# Grove_-_Finger-clip_Heart_Rate_Sensor_v1.net
KiCad netlist of a schematic drawn in EAGLE
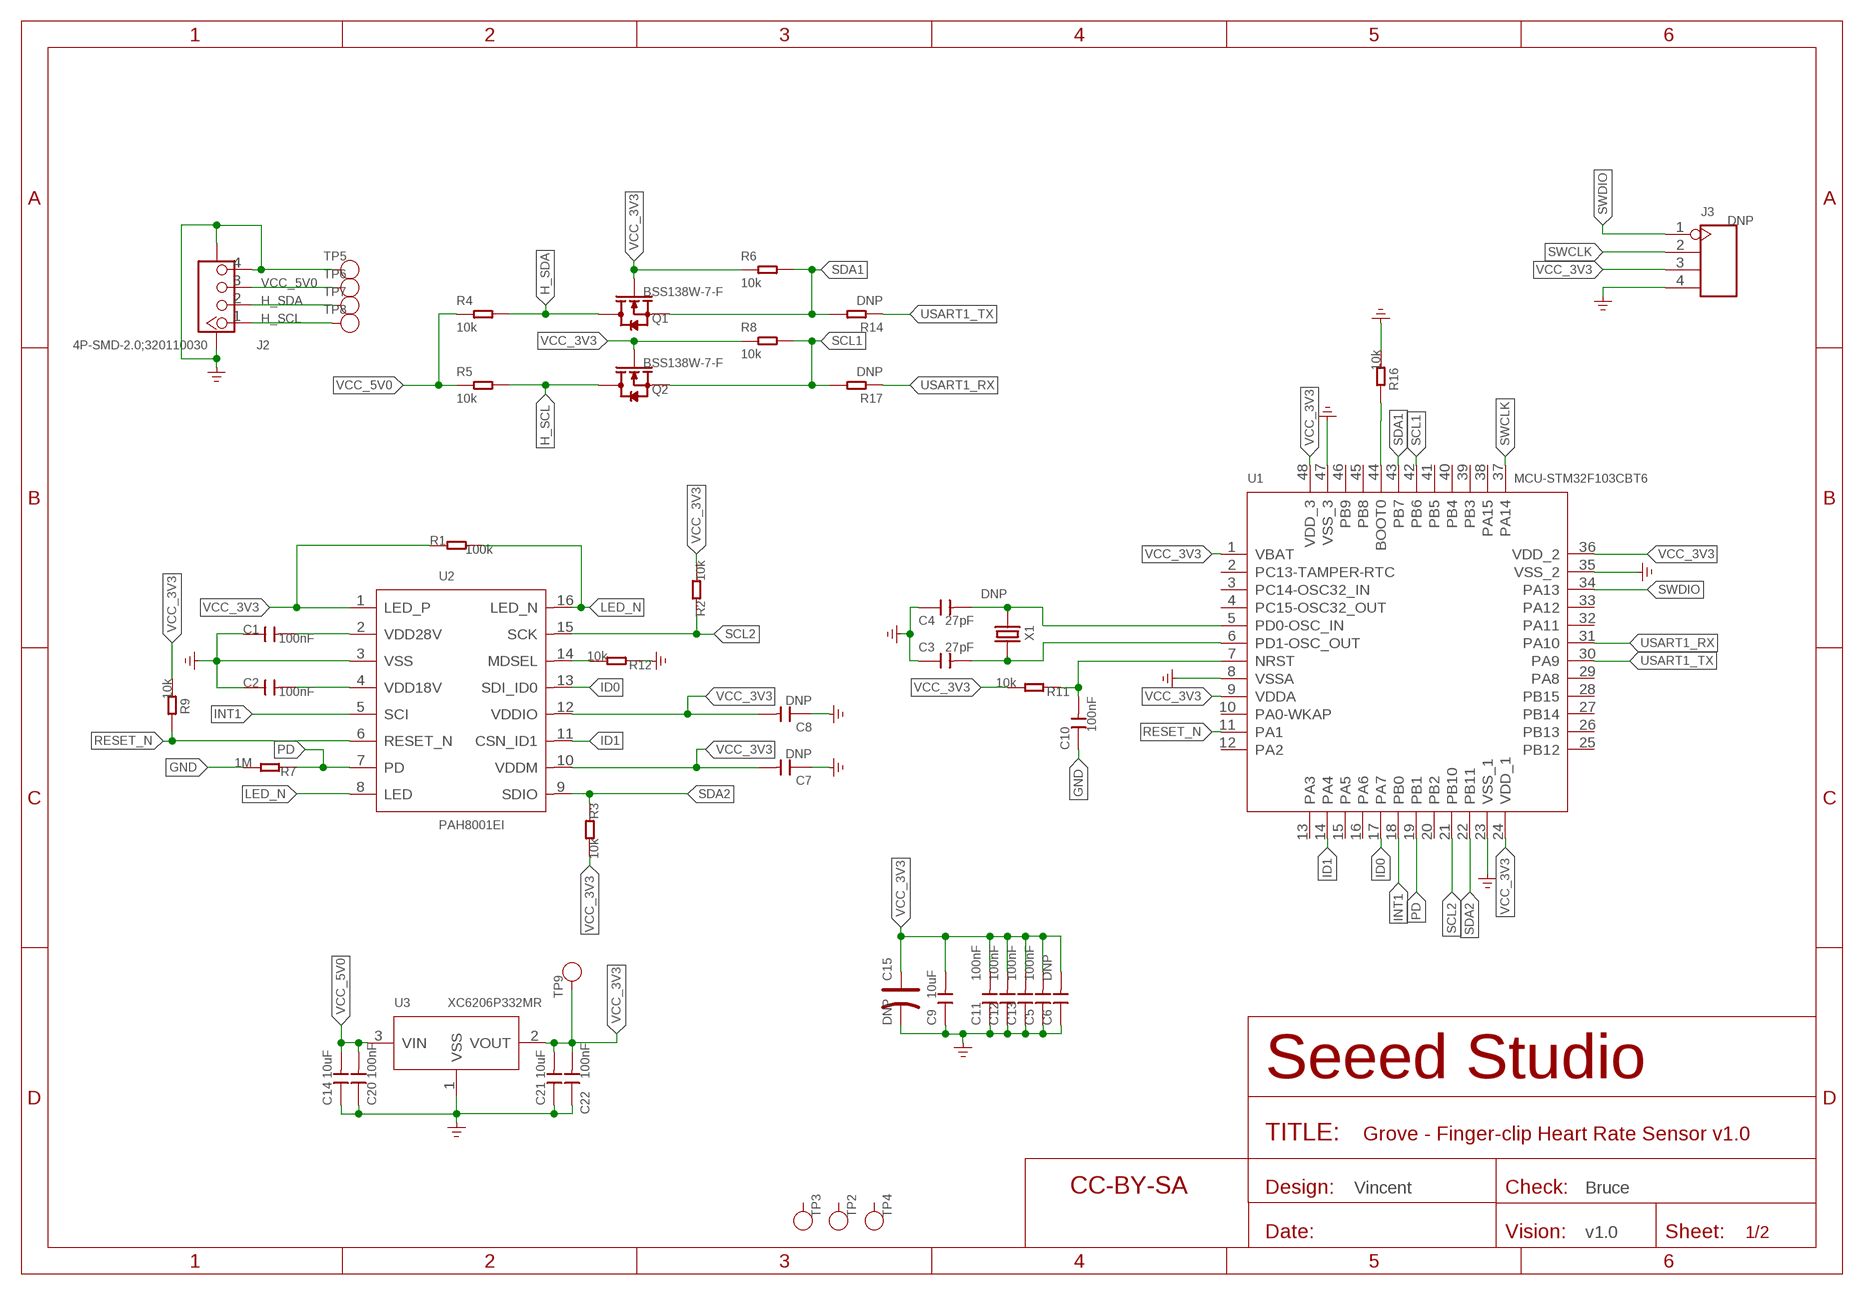
[diagram p0: schematic, sheet 1]

(export (version "E")
  (design (tool "Eeschema 10.0.6"))
  (components
    (comp (ref "C1")
      (value "100nF")
      (footprint "eagle-import:C0402")
      (libsource (lib "eagle-import") (part "CAP-0402"))
    )
    (comp (ref "C2")
      (value "100nF")
      (footprint "eagle-import:C0402")
      (libsource (lib "eagle-import") (part "CAP-0402"))
    )
    (comp (ref "C3")
      (value "27pF")
      (footprint "eagle-import:C0402")
      (libsource (lib "eagle-import") (part "CAP-0402"))
    )
    (comp (ref "C4")
      (value "27pF")
      (footprint "eagle-import:C0402")
      (libsource (lib "eagle-import") (part "CAP-0402"))
    )
    (comp (ref "C5")
      (value "100nF")
      (footprint "eagle-import:C0402")
      (libsource (lib "eagle-import") (part "CAP-0402"))
    )
    (comp (ref "C6")
      (value "DNP")
      (footprint "eagle-import:C0402")
      (libsource (lib "eagle-import") (part "CAP-0402"))
    )
    (comp (ref "C7")
      (value "DNP")
      (footprint "eagle-import:C0402")
      (libsource (lib "eagle-import") (part "CAP-0402"))
    )
    (comp (ref "C8")
      (value "DNP")
      (footprint "eagle-import:C0402")
      (libsource (lib "eagle-import") (part "CAP-0402"))
    )
    (comp (ref "C9")
      (value "10uF")
      (footprint "eagle-import:C0603")
      (libsource (lib "eagle-import") (part "CAP-0603"))
    )
    (comp (ref "C10")
      (value "100nF")
      (footprint "eagle-import:C0402")
      (libsource (lib "eagle-import") (part "CAP-0402"))
    )
    (comp (ref "C11")
      (value "100nF")
      (footprint "eagle-import:C0402")
      (libsource (lib "eagle-import") (part "CAP-0402"))
    )
    (comp (ref "C12")
      (value "100nF")
      (footprint "eagle-import:C0402")
      (libsource (lib "eagle-import") (part "CAP-0402"))
    )
    (comp (ref "C13")
      (value "100nF")
      (footprint "eagle-import:C0402")
      (libsource (lib "eagle-import") (part "CAP-0402"))
    )
    (comp (ref "C14")
      (value "10uF")
      (footprint "eagle-import:C0603")
      (libsource (lib "eagle-import") (part "CAP-0603"))
    )
    (comp (ref "C15")
      (value "DNP")
      (footprint "eagle-import:AVX-A")
      (libsource (lib "eagle-import") (part "CAP-POLAR-AVX-A"))
    )
    (comp (ref "C20")
      (value "100nF")
      (footprint "eagle-import:C0402")
      (libsource (lib "eagle-import") (part "CAP-0402"))
    )
    (comp (ref "C21")
      (value "10uF")
      (footprint "eagle-import:C0603")
      (libsource (lib "eagle-import") (part "CAP-0603"))
    )
    (comp (ref "C22")
      (value "100nF")
      (footprint "eagle-import:C0402")
      (libsource (lib "eagle-import") (part "CAP-0402"))
    )
    (comp (ref "J2")
      (value "4P-SMD-2.0;320110030")
      (footprint "eagle-import:4P-SMD-2.0")
      (libsource (lib "eagle-import") (part "GROVE-CONNECTOR-SMD'DD'"))
    )
    (comp (ref "J3")
      (value "DNP")
      (footprint "eagle-import:4P-2.54-65_35MIL")
      (libsource (lib "eagle-import") (part "HEADER-4P-65/35MIL"))
    )
    (comp (ref "Q1")
      (value "BSS138W-7-F")
      (footprint "eagle-import:SOT-323")
      (libsource (lib "eagle-import") (part "MOSFET-N'SI1304BDL'"))
    )
    (comp (ref "Q2")
      (value "BSS138W-7-F")
      (footprint "eagle-import:SOT-323")
      (libsource (lib "eagle-import") (part "MOSFET-N'SI1304BDL'"))
    )
    (comp (ref "R1")
      (value "100k")
      (footprint "eagle-import:R0402")
      (libsource (lib "eagle-import") (part "RES-0402"))
    )
    (comp (ref "R2")
      (value "10k")
      (footprint "eagle-import:R0402")
      (libsource (lib "eagle-import") (part "RES-0402"))
    )
    (comp (ref "R3")
      (value "10k")
      (footprint "eagle-import:R0402")
      (libsource (lib "eagle-import") (part "RES-0402"))
    )
    (comp (ref "R4")
      (value "10k")
      (footprint "eagle-import:R0402")
      (libsource (lib "eagle-import") (part "RES-0402"))
    )
    (comp (ref "R5")
      (value "10k")
      (footprint "eagle-import:R0402")
      (libsource (lib "eagle-import") (part "RES-0402"))
    )
    (comp (ref "R6")
      (value "10k")
      (footprint "eagle-import:R0402")
      (libsource (lib "eagle-import") (part "RES-0402"))
    )
    (comp (ref "R7")
      (value "1M")
      (footprint "eagle-import:R0402")
      (libsource (lib "eagle-import") (part "RES-0402"))
    )
    (comp (ref "R8")
      (value "10k")
      (footprint "eagle-import:R0402")
      (libsource (lib "eagle-import") (part "RES-0402"))
    )
    (comp (ref "R9")
      (value "10k")
      (footprint "eagle-import:R0402")
      (libsource (lib "eagle-import") (part "RES-0402"))
    )
    (comp (ref "R11")
      (value "10k")
      (footprint "eagle-import:R0402")
      (libsource (lib "eagle-import") (part "RES-0402"))
    )
    (comp (ref "R12")
      (value "10k")
      (footprint "eagle-import:R0402")
      (libsource (lib "eagle-import") (part "RES-0402"))
    )
    (comp (ref "R14")
      (value "DNP")
      (footprint "eagle-import:R0402")
      (libsource (lib "eagle-import") (part "RES-0402"))
    )
    (comp (ref "R16")
      (value "10k")
      (footprint "eagle-import:R0402")
      (libsource (lib "eagle-import") (part "RES-0402"))
    )
    (comp (ref "R17")
      (value "DNP")
      (footprint "eagle-import:R0402")
      (libsource (lib "eagle-import") (part "RES-0402"))
    )
    (comp (ref "TP2")
      (value "DNP")
      (footprint "eagle-import:TP-D45MIL")
      (libsource (lib "eagle-import") (part "PAD-TEST-POINT'4545'"))
    )
    (comp (ref "TP3")
      (value "DNP")
      (footprint "eagle-import:TP-D45MIL")
      (libsource (lib "eagle-import") (part "PAD-TEST-POINT'4545'"))
    )
    (comp (ref "TP4")
      (value "DNP")
      (footprint "eagle-import:TP-D45MIL")
      (libsource (lib "eagle-import") (part "PAD-TEST-POINT'4545'"))
    )
    (comp (ref "TP5")
      (value "DNP")
      (footprint "eagle-import:TP-D45MIL")
      (libsource (lib "eagle-import") (part "PAD-TEST-POINT'4545'"))
    )
    (comp (ref "TP6")
      (value "DNP")
      (footprint "eagle-import:TP-D45MIL")
      (libsource (lib "eagle-import") (part "PAD-TEST-POINT'4545'"))
    )
    (comp (ref "TP7")
      (value "DNP")
      (footprint "eagle-import:TP-D45MIL")
      (libsource (lib "eagle-import") (part "PAD-TEST-POINT'4545'"))
    )
    (comp (ref "TP8")
      (value "DNP")
      (footprint "eagle-import:TP-D45MIL")
      (libsource (lib "eagle-import") (part "PAD-TEST-POINT'4545'"))
    )
    (comp (ref "TP9")
      (value "DNP")
      (footprint "eagle-import:TP-D45MIL")
      (libsource (lib "eagle-import") (part "PAD-TEST-POINT'4545'"))
    )
    (comp (ref "U$1")
      (value "SEEEDSTUDIO-OPEN-SCH-FRAME")
      (footprint "eagle-import:SEEEDSTUDIO-PCB-FRAME")
      (libsource (lib "eagle-import") (part "SEEEDSTUDIO-OPEN-SCH-FRAME"))
    )
    (comp (ref "U1")
      (value "MCU-STM32F103CBT6")
      (footprint "eagle-import:TEMPLATE_LQFP48")
      (libsource (lib "eagle-import") (part "TEMPLATE_MCU-STM32F103CBT6"))
    )
    (comp (ref "U2")
      (value "PAH8001EI")
      (footprint "eagle-import:16P-SMD-L4.7_W3_H1MM")
      (libsource (lib "eagle-import") (part "PAH8001EI-QG"))
    )
    (comp (ref "U3")
      (value "XC6206P332MR")
      (footprint "eagle-import:SOT-23")
      (libsource (lib "eagle-import") (part "PMIC-XC6206PMR"))
    )
    (comp (ref "X1")
      (value "DNP")
      (footprint "eagle-import:2P-SMD-L5.0_W3.2MM")
      (libsource (lib "eagle-import") (part "CRYSTAL'5032'"))
    )
  )
  (nets
    (net (code "1") (name "BOOT0") (class "Default")
      (node (ref "R16") (pin "2") (pinfunction "2_2") (pintype "passive"))
      (node (ref "U1") (pin "44") (pinfunction "BOOT0_44") (pintype "bidirectional"))
    )
    (net (code "2") (name "GND") (class "Default")
      (node (ref "C1") (pin "1") (pinfunction "1_1") (pintype "passive"))
      (node (ref "C10") (pin "1") (pinfunction "1_1") (pintype "passive"))
      (node (ref "C11") (pin "1") (pinfunction "1_1") (pintype "passive"))
      (node (ref "C12") (pin "1") (pinfunction "1_1") (pintype "passive"))
      (node (ref "C13") (pin "1") (pinfunction "1_1") (pintype "passive"))
      (node (ref "C14") (pin "1") (pinfunction "1_1") (pintype "passive"))
      (node (ref "C15") (pin "-") (pinfunction "-_-") (pintype "passive"))
      (node (ref "C2") (pin "1") (pinfunction "1_1") (pintype "passive"))
      (node (ref "C20") (pin "1") (pinfunction "1_1") (pintype "passive"))
      (node (ref "C21") (pin "1") (pinfunction "1_1") (pintype "passive"))
      (node (ref "C22") (pin "1") (pinfunction "1_1") (pintype "passive"))
      (node (ref "C3") (pin "1") (pinfunction "1_1") (pintype "passive"))
      (node (ref "C4") (pin "1") (pinfunction "1_1") (pintype "passive"))
      (node (ref "C5") (pin "1") (pinfunction "1_1") (pintype "passive"))
      (node (ref "C6") (pin "1") (pinfunction "1_1") (pintype "passive"))
      (node (ref "C7") (pin "1") (pinfunction "1_1") (pintype "passive"))
      (node (ref "C8") (pin "1") (pinfunction "1_1") (pintype "passive"))
      (node (ref "C9") (pin "1") (pinfunction "1_1") (pintype "passive"))
      (node (ref "J2") (pin "4") (pinfunction "4_4") (pintype "bidirectional"))
      (node (ref "J2") (pin "SS1") (pinfunction "SS1_SS1") (pintype "bidirectional"))
      (node (ref "J2") (pin "SS2") (pinfunction "SS2_SS2") (pintype "bidirectional"))
      (node (ref "J3") (pin "4") (pinfunction "P$4_4") (pintype "bidirectional"))
      (node (ref "R12") (pin "1") (pinfunction "1_1") (pintype "passive"))
      (node (ref "R16") (pin "1") (pinfunction "1_1") (pintype "passive"))
      (node (ref "R7") (pin "2") (pinfunction "2_2") (pintype "passive"))
      (node (ref "TP5") (pin "T") (pinfunction "T_T") (pintype "bidirectional"))
      (node (ref "U1") (pin "23") (pinfunction "VSS_1_23") (pintype "bidirectional"))
      (node (ref "U1") (pin "35") (pinfunction "VSS_2_35") (pintype "bidirectional"))
      (node (ref "U1") (pin "47") (pinfunction "VSS_3_47") (pintype "bidirectional"))
      (node (ref "U1") (pin "8") (pinfunction "VSSA_8") (pintype "bidirectional"))
      (node (ref "U2") (pin "3") (pinfunction "VSS_3") (pintype "bidirectional"))
      (node (ref "U3") (pin "1") (pinfunction "VSS_1") (pintype "power_in"))
    )
    (net (code "3") (name "H_SCL") (class "Default")
      (node (ref "J2") (pin "1") (pinfunction "1_1") (pintype "bidirectional"))
      (node (ref "Q2") (pin "3") (pinfunction "D_3") (pintype "passive"))
      (node (ref "R5") (pin "2") (pinfunction "2_2") (pintype "passive"))
      (node (ref "TP8") (pin "T") (pinfunction "T_T") (pintype "bidirectional"))
    )
    (net (code "4") (name "H_SDA") (class "Default")
      (node (ref "J2") (pin "2") (pinfunction "2_2") (pintype "bidirectional"))
      (node (ref "Q1") (pin "3") (pinfunction "D_3") (pintype "passive"))
      (node (ref "R4") (pin "2") (pinfunction "2_2") (pintype "passive"))
      (node (ref "TP7") (pin "T") (pinfunction "T_T") (pintype "bidirectional"))
    )
    (net (code "5") (name "ID0") (class "Default")
      (node (ref "U1") (pin "17") (pinfunction "PA7_17") (pintype "bidirectional"))
      (node (ref "U2") (pin "13") (pinfunction "SDI_ID0_13") (pintype "bidirectional"))
    )
    (net (code "6") (name "ID1") (class "Default")
      (node (ref "U1") (pin "14") (pinfunction "PA4_14") (pintype "bidirectional"))
      (node (ref "U2") (pin "11") (pinfunction "CSN_ID1_11") (pintype "bidirectional"))
    )
    (net (code "7") (name "INT1") (class "Default")
      (node (ref "U1") (pin "18") (pinfunction "PB0_18") (pintype "bidirectional"))
      (node (ref "U2") (pin "5") (pinfunction "SCI_5") (pintype "bidirectional"))
    )
    (net (code "8") (name "LED_N") (class "Default")
      (node (ref "R1") (pin "2") (pinfunction "2_2") (pintype "passive"))
      (node (ref "U2") (pin "16") (pinfunction "LED_N_16") (pintype "bidirectional"))
      (node (ref "U2") (pin "8") (pinfunction "LED_8") (pintype "bidirectional"))
    )
    (net (code "9") (name "Net-(U1-NRST)") (class "Default")
      (node (ref "C10") (pin "2") (pinfunction "2_2") (pintype "passive"))
      (node (ref "R11") (pin "1") (pinfunction "1_1") (pintype "passive"))
      (node (ref "U1") (pin "7") (pinfunction "NRST_7") (pintype "bidirectional"))
    )
    (net (code "10") (name "Net-(U1-PD0-OSC_IN)") (class "Default")
      (node (ref "C4") (pin "2") (pinfunction "2_2") (pintype "passive"))
      (node (ref "U1") (pin "5") (pinfunction "PD0-OSC_IN_5") (pintype "bidirectional"))
      (node (ref "X1") (pin "1") (pinfunction "1_1") (pintype "passive"))
    )
    (net (code "11") (name "Net-(U1-PD1-OSC_OUT)") (class "Default")
      (node (ref "C3") (pin "2") (pinfunction "2_2") (pintype "passive"))
      (node (ref "U1") (pin "6") (pinfunction "PD1-OSC_OUT_6") (pintype "bidirectional"))
      (node (ref "X1") (pin "2") (pinfunction "2_2") (pintype "passive"))
    )
    (net (code "12") (name "Net-(U2-MDSEL)") (class "Default")
      (node (ref "R12") (pin "2") (pinfunction "2_2") (pintype "passive"))
      (node (ref "U2") (pin "14") (pinfunction "MDSEL_14") (pintype "bidirectional"))
    )
    (net (code "13") (name "Net-(U2-VDD18V)") (class "Default")
      (node (ref "C2") (pin "2") (pinfunction "2_2") (pintype "passive"))
      (node (ref "U2") (pin "4") (pinfunction "VDD18V_4") (pintype "bidirectional"))
    )
    (net (code "14") (name "Net-(U2-VDD28V)") (class "Default")
      (node (ref "C1") (pin "2") (pinfunction "2_2") (pintype "passive"))
      (node (ref "U2") (pin "2") (pinfunction "VDD28V_2") (pintype "bidirectional"))
    )
    (net (code "15") (name "PD") (class "Default")
      (node (ref "R7") (pin "1") (pinfunction "1_1") (pintype "passive"))
      (node (ref "U1") (pin "19") (pinfunction "PB1_19") (pintype "bidirectional"))
      (node (ref "U2") (pin "7") (pinfunction "PD_7") (pintype "bidirectional"))
    )
    (net (code "16") (name "RESET_N") (class "Default")
      (node (ref "R9") (pin "2") (pinfunction "2_2") (pintype "passive"))
      (node (ref "U1") (pin "11") (pinfunction "PA1_11") (pintype "bidirectional"))
      (node (ref "U2") (pin "6") (pinfunction "RESET_N_6") (pintype "bidirectional"))
    )
    (net (code "17") (name "SCL1") (class "Default")
      (node (ref "Q2") (pin "2") (pinfunction "S_2") (pintype "passive"))
      (node (ref "R17") (pin "2") (pinfunction "2_2") (pintype "passive"))
      (node (ref "R8") (pin "2") (pinfunction "2_2") (pintype "passive"))
      (node (ref "U1") (pin "42") (pinfunction "PB6_42") (pintype "bidirectional"))
    )
    (net (code "18") (name "SCL2") (class "Default")
      (node (ref "R2") (pin "1") (pinfunction "1_1") (pintype "passive"))
      (node (ref "U1") (pin "21") (pinfunction "PB10_21") (pintype "bidirectional"))
      (node (ref "U2") (pin "15") (pinfunction "SCK_15") (pintype "bidirectional"))
    )
    (net (code "19") (name "SDA1") (class "Default")
      (node (ref "Q1") (pin "2") (pinfunction "S_2") (pintype "passive"))
      (node (ref "R14") (pin "2") (pinfunction "2_2") (pintype "passive"))
      (node (ref "R6") (pin "2") (pinfunction "2_2") (pintype "passive"))
      (node (ref "U1") (pin "43") (pinfunction "PB7_43") (pintype "bidirectional"))
    )
    (net (code "20") (name "SDA2") (class "Default")
      (node (ref "R3") (pin "1") (pinfunction "1_1") (pintype "passive"))
      (node (ref "U1") (pin "22") (pinfunction "PB11_22") (pintype "bidirectional"))
      (node (ref "U2") (pin "9") (pinfunction "SDIO_9") (pintype "bidirectional"))
    )
    (net (code "21") (name "SWCLK") (class "Default")
      (node (ref "J3") (pin "2") (pinfunction "P$2_2") (pintype "bidirectional"))
      (node (ref "U1") (pin "37") (pinfunction "PA14_37") (pintype "bidirectional"))
    )
    (net (code "22") (name "SWDIO") (class "Default")
      (node (ref "J3") (pin "1") (pinfunction "P$1_1") (pintype "bidirectional"))
      (node (ref "U1") (pin "34") (pinfunction "PA13_34") (pintype "bidirectional"))
    )
    (net (code "23") (name "USART1_RX") (class "Default")
      (node (ref "R17") (pin "1") (pinfunction "1_1") (pintype "passive"))
      (node (ref "U1") (pin "31") (pinfunction "PA10_31") (pintype "bidirectional"))
    )
    (net (code "24") (name "USART1_TX") (class "Default")
      (node (ref "R14") (pin "1") (pinfunction "1_1") (pintype "passive"))
      (node (ref "U1") (pin "30") (pinfunction "PA9_30") (pintype "bidirectional"))
    )
    (net (code "25") (name "VCC_3V3") (class "Default")
      (node (ref "C11") (pin "2") (pinfunction "2_2") (pintype "passive"))
      (node (ref "C12") (pin "2") (pinfunction "2_2") (pintype "passive"))
      (node (ref "C13") (pin "2") (pinfunction "2_2") (pintype "passive"))
      (node (ref "C15") (pin "+") (pinfunction "+_+") (pintype "passive"))
      (node (ref "C21") (pin "2") (pinfunction "2_2") (pintype "passive"))
      (node (ref "C22") (pin "2") (pinfunction "2_2") (pintype "passive"))
      (node (ref "C5") (pin "2") (pinfunction "2_2") (pintype "passive"))
      (node (ref "C6") (pin "2") (pinfunction "2_2") (pintype "passive"))
      (node (ref "C7") (pin "2") (pinfunction "2_2") (pintype "passive"))
      (node (ref "C8") (pin "2") (pinfunction "2_2") (pintype "passive"))
      (node (ref "C9") (pin "2") (pinfunction "2_2") (pintype "passive"))
      (node (ref "J3") (pin "3") (pinfunction "P$3_3") (pintype "bidirectional"))
      (node (ref "Q1") (pin "1") (pinfunction "G_1") (pintype "passive"))
      (node (ref "Q2") (pin "1") (pinfunction "G_1") (pintype "passive"))
      (node (ref "R1") (pin "1") (pinfunction "1_1") (pintype "passive"))
      (node (ref "R11") (pin "2") (pinfunction "2_2") (pintype "passive"))
      (node (ref "R2") (pin "2") (pinfunction "2_2") (pintype "passive"))
      (node (ref "R3") (pin "2") (pinfunction "2_2") (pintype "passive"))
      (node (ref "R6") (pin "1") (pinfunction "1_1") (pintype "passive"))
      (node (ref "R8") (pin "1") (pinfunction "1_1") (pintype "passive"))
      (node (ref "R9") (pin "1") (pinfunction "1_1") (pintype "passive"))
      (node (ref "TP9") (pin "T") (pinfunction "T_T") (pintype "bidirectional"))
      (node (ref "U1") (pin "1") (pinfunction "VBAT_1") (pintype "bidirectional"))
      (node (ref "U1") (pin "24") (pinfunction "VDD_1_24") (pintype "bidirectional"))
      (node (ref "U1") (pin "36") (pinfunction "VDD_2_36") (pintype "bidirectional"))
      (node (ref "U1") (pin "48") (pinfunction "VDD_3_48") (pintype "bidirectional"))
      (node (ref "U1") (pin "9") (pinfunction "VDDA_9") (pintype "bidirectional"))
      (node (ref "U2") (pin "1") (pinfunction "LED_P_1") (pintype "bidirectional"))
      (node (ref "U2") (pin "10") (pinfunction "VDDM_10") (pintype "bidirectional"))
      (node (ref "U2") (pin "12") (pinfunction "VDDIO_12") (pintype "bidirectional"))
      (node (ref "U3") (pin "2") (pinfunction "VOUT_2") (pintype "output"))
    )
    (net (code "26") (name "VCC_5V0") (class "Default")
      (node (ref "C14") (pin "2") (pinfunction "2_2") (pintype "passive"))
      (node (ref "C20") (pin "2") (pinfunction "2_2") (pintype "passive"))
      (node (ref "J2") (pin "3") (pinfunction "3_3") (pintype "bidirectional"))
      (node (ref "R4") (pin "1") (pinfunction "1_1") (pintype "passive"))
      (node (ref "R5") (pin "1") (pinfunction "1_1") (pintype "passive"))
      (node (ref "TP6") (pin "T") (pinfunction "T_T") (pintype "bidirectional"))
      (node (ref "U3") (pin "3") (pinfunction "VIN_3") (pintype "input"))
    )
    (net (code "27") (name "unconnected-(TP2-PadT)") (class "Default")
      (node (ref "TP2") (pin "T") (pinfunction "T_T") (pintype "bidirectional"))
    )
    (net (code "28") (name "unconnected-(TP3-PadT)") (class "Default")
      (node (ref "TP3") (pin "T") (pinfunction "T_T") (pintype "bidirectional"))
    )
    (net (code "29") (name "unconnected-(TP4-PadT)") (class "Default")
      (node (ref "TP4") (pin "T") (pinfunction "T_T") (pintype "bidirectional"))
    )
    (net (code "30") (name "unconnected-(U1-PA0-WKAP-Pad10)") (class "Default")
      (node (ref "U1") (pin "10") (pinfunction "PA0-WKAP_10") (pintype "bidirectional"))
    )
    (net (code "31") (name "unconnected-(U1-PA2-Pad12)") (class "Default")
      (node (ref "U1") (pin "12") (pinfunction "PA2_12") (pintype "bidirectional"))
    )
    (net (code "32") (name "unconnected-(U1-PA3-Pad13)") (class "Default")
      (node (ref "U1") (pin "13") (pinfunction "PA3_13") (pintype "bidirectional"))
    )
    (net (code "33") (name "unconnected-(U1-PA5-Pad15)") (class "Default")
      (node (ref "U1") (pin "15") (pinfunction "PA5_15") (pintype "bidirectional"))
    )
    (net (code "34") (name "unconnected-(U1-PA6-Pad16)") (class "Default")
      (node (ref "U1") (pin "16") (pinfunction "PA6_16") (pintype "bidirectional"))
    )
    (net (code "35") (name "unconnected-(U1-PA8-Pad29)") (class "Default")
      (node (ref "U1") (pin "29") (pinfunction "PA8_29") (pintype "bidirectional"))
    )
    (net (code "36") (name "unconnected-(U1-PA11-Pad32)") (class "Default")
      (node (ref "U1") (pin "32") (pinfunction "PA11_32") (pintype "bidirectional"))
    )
    (net (code "37") (name "unconnected-(U1-PA12-Pad33)") (class "Default")
      (node (ref "U1") (pin "33") (pinfunction "PA12_33") (pintype "bidirectional"))
    )
    (net (code "38") (name "unconnected-(U1-PA15-Pad38)") (class "Default")
      (node (ref "U1") (pin "38") (pinfunction "PA15_38") (pintype "bidirectional"))
    )
    (net (code "39") (name "unconnected-(U1-PB2-Pad20)") (class "Default")
      (node (ref "U1") (pin "20") (pinfunction "PB2_20") (pintype "bidirectional"))
    )
    (net (code "40") (name "unconnected-(U1-PB3-Pad39)") (class "Default")
      (node (ref "U1") (pin "39") (pinfunction "PB3_39") (pintype "bidirectional"))
    )
    (net (code "41") (name "unconnected-(U1-PB4-Pad40)") (class "Default")
      (node (ref "U1") (pin "40") (pinfunction "PB4_40") (pintype "bidirectional"))
    )
    (net (code "42") (name "unconnected-(U1-PB5-Pad41)") (class "Default")
      (node (ref "U1") (pin "41") (pinfunction "PB5_41") (pintype "bidirectional"))
    )
    (net (code "43") (name "unconnected-(U1-PB8-Pad45)") (class "Default")
      (node (ref "U1") (pin "45") (pinfunction "PB8_45") (pintype "bidirectional"))
    )
    (net (code "44") (name "unconnected-(U1-PB9-Pad46)") (class "Default")
      (node (ref "U1") (pin "46") (pinfunction "PB9_46") (pintype "bidirectional"))
    )
    (net (code "45") (name "unconnected-(U1-PB12-Pad25)") (class "Default")
      (node (ref "U1") (pin "25") (pinfunction "PB12_25") (pintype "bidirectional"))
    )
    (net (code "46") (name "unconnected-(U1-PB13-Pad26)") (class "Default")
      (node (ref "U1") (pin "26") (pinfunction "PB13_26") (pintype "bidirectional"))
    )
    (net (code "47") (name "unconnected-(U1-PB14-Pad27)") (class "Default")
      (node (ref "U1") (pin "27") (pinfunction "PB14_27") (pintype "bidirectional"))
    )
    (net (code "48") (name "unconnected-(U1-PB15-Pad28)") (class "Default")
      (node (ref "U1") (pin "28") (pinfunction "PB15_28") (pintype "bidirectional"))
    )
    (net (code "49") (name "unconnected-(U1-PC13-TAMPER-RTC-Pad2)") (class "Default")
      (node (ref "U1") (pin "2") (pinfunction "PC13-TAMPER-RTC_2") (pintype "bidirectional"))
    )
    (net (code "50") (name "unconnected-(U1-PC14-OSC32_IN-Pad3)") (class "Default")
      (node (ref "U1") (pin "3") (pinfunction "PC14-OSC32_IN_3") (pintype "bidirectional"))
    )
    (net (code "51") (name "unconnected-(U1-PC15-OSC32_OUT-Pad4)") (class "Default")
      (node (ref "U1") (pin "4") (pinfunction "PC15-OSC32_OUT_4") (pintype "bidirectional"))
    )
  )
)
